# Atmega328p_Breakout.net
KiCad netlist of a schematic drawn in Altium Designer
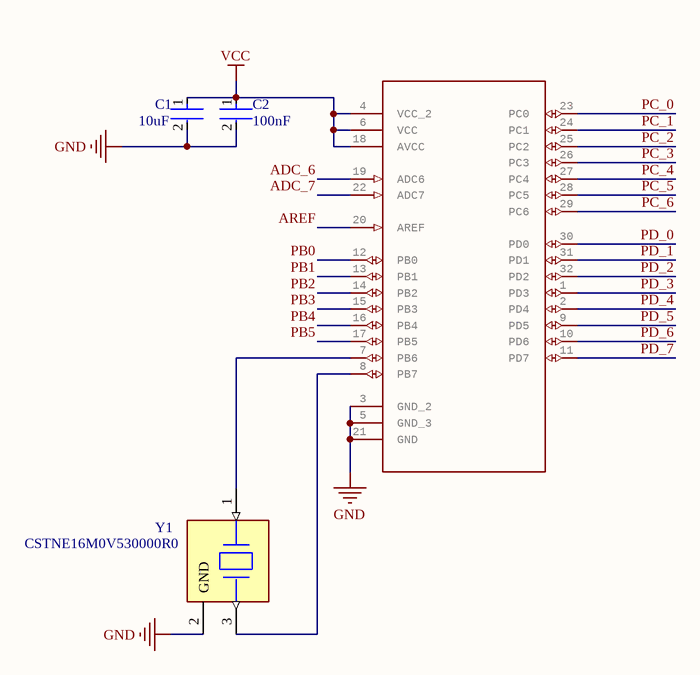
[diagram p0: Atmega328p_Breakout.SchDoc]

(export (version "E")
  (design (tool "Eeschema 10.0.6"))
  (components
    (comp (ref "C1")
      (value "10uF")
      (footprint "FP-CC0805-0_85-MFG")
      (description "CAP CER 0.1UF 50V X7R 0805")
      (fields (field (name "TOLERANCE") "0.1") (field (name "MANUFACTURER PART NUMBER") "CC0805KRX7R9BB104"))
      (libsource (lib "Altium Content Vault") (part "11868f565c42a9108669ba33697ecf6"))
    )
    (comp (ref "C2")
      (value "100nF")
      (footprint "FP-CC0805-0_85-MFG")
      (description "CAP CER 0.1UF 50V X7R 0805")
      (fields (field (name "TOLERANCE") "0.1") (field (name "MANUFACTURER PART NUMBER") "CC0805KRX7R9BB104"))
      (libsource (lib "Altium Content Vault") (part "11868f565c42a9108669ba33697ecf6"))
    )
    (comp (ref "U1")
      (value "ATMEL-ATMEGA328P-AU_ATMEGA328P-AU")
      (footprint "ATMEL-ATMEGA328P-AU_QFP80P900X900X120-32N")
      (fields (field (name "MPN") "ATMEGA328P-AU") (field (name "LIBRARYNAME") "AmbaSat-1v1-01-NO-solar"))
      (libsource (lib "Chip_kz85") (part "ATMEL-ATMEGA328P-AU_ATMEGA328P-AU"))
    )
    (comp (ref "Y1")
      (value "CSTNE16M0V530000R0")
      (footprint "FP-CSTNE16M0V530000R0-MFG")
      (description "16MHz Ceramic Resonator Built in Capacitor 15pF ±0.3% 40 Ohms -40°C ~ 85°C Surface Mount")
      (fields (field (name "TOLERANCE") "0.5%"))
      (libsource (lib "Altium Content Vault") (part "f88508b02107a2c8e6f46217c19d2b8"))
    )
  )
  (nets
    (net (code "1") (name "/ADC_6") (class "Default")
      (node (ref "U1") (pin "19") (pinfunction "ADC6_19") (pintype "input"))
    )
    (net (code "2") (name "/ADC_7") (class "Default")
      (node (ref "U1") (pin "22") (pinfunction "ADC7_22") (pintype "input"))
    )
    (net (code "3") (name "/AREF") (class "Default")
      (node (ref "U1") (pin "20") (pinfunction "AREF_20") (pintype "input"))
    )
    (net (code "4") (name "/PB0") (class "Default")
      (node (ref "U1") (pin "12") (pinfunction "PB0_12") (pintype "bidirectional"))
    )
    (net (code "5") (name "/PB1") (class "Default")
      (node (ref "U1") (pin "13") (pinfunction "PB1_13") (pintype "bidirectional"))
    )
    (net (code "6") (name "/PB2") (class "Default")
      (node (ref "U1") (pin "14") (pinfunction "PB2_14") (pintype "bidirectional"))
    )
    (net (code "7") (name "/PB3") (class "Default")
      (node (ref "U1") (pin "15") (pinfunction "PB3_15") (pintype "bidirectional"))
    )
    (net (code "8") (name "/PB4") (class "Default")
      (node (ref "U1") (pin "16") (pinfunction "PB4_16") (pintype "bidirectional"))
    )
    (net (code "9") (name "/PB5") (class "Default")
      (node (ref "U1") (pin "17") (pinfunction "PB5_17") (pintype "bidirectional"))
    )
    (net (code "10") (name "/PC_0") (class "Default")
      (node (ref "U1") (pin "23") (pinfunction "PC0_23") (pintype "bidirectional"))
    )
    (net (code "11") (name "/PC_1") (class "Default")
      (node (ref "U1") (pin "24") (pinfunction "PC1_24") (pintype "bidirectional"))
    )
    (net (code "12") (name "/PC_2") (class "Default")
      (node (ref "U1") (pin "25") (pinfunction "PC2_25") (pintype "bidirectional"))
    )
    (net (code "13") (name "/PC_3") (class "Default")
      (node (ref "U1") (pin "26") (pinfunction "PC3_26") (pintype "bidirectional"))
    )
    (net (code "14") (name "/PC_4") (class "Default")
      (node (ref "U1") (pin "27") (pinfunction "PC4_27") (pintype "bidirectional"))
    )
    (net (code "15") (name "/PC_5") (class "Default")
      (node (ref "U1") (pin "28") (pinfunction "PC5_28") (pintype "bidirectional"))
    )
    (net (code "16") (name "/PC_6") (class "Default")
      (node (ref "U1") (pin "29") (pinfunction "PC6_29") (pintype "bidirectional"))
    )
    (net (code "17") (name "/PD_0") (class "Default")
      (node (ref "U1") (pin "30") (pinfunction "PD0_30") (pintype "bidirectional"))
    )
    (net (code "18") (name "/PD_1") (class "Default")
      (node (ref "U1") (pin "31") (pinfunction "PD1_31") (pintype "bidirectional"))
    )
    (net (code "19") (name "/PD_2") (class "Default")
      (node (ref "U1") (pin "32") (pinfunction "PD2_32") (pintype "bidirectional"))
    )
    (net (code "20") (name "/PD_3") (class "Default")
      (node (ref "U1") (pin "1") (pinfunction "PD3_1") (pintype "bidirectional"))
    )
    (net (code "21") (name "/PD_4") (class "Default")
      (node (ref "U1") (pin "2") (pinfunction "PD4_2") (pintype "bidirectional"))
    )
    (net (code "22") (name "/PD_5") (class "Default")
      (node (ref "U1") (pin "9") (pinfunction "PD5_9") (pintype "bidirectional"))
    )
    (net (code "23") (name "/PD_6") (class "Default")
      (node (ref "U1") (pin "10") (pinfunction "PD6_10") (pintype "bidirectional"))
    )
    (net (code "24") (name "/PD_7") (class "Default")
      (node (ref "U1") (pin "11") (pinfunction "PD7_11") (pintype "bidirectional"))
    )
    (net (code "25") (name "GND") (class "Default")
      (node (ref "C1") (pin "2") (pinfunction "2_2") (pintype "passive"))
      (node (ref "C2") (pin "2") (pinfunction "2_2") (pintype "passive"))
      (node (ref "U1") (pin "21") (pinfunction "GND_21") (pintype "passive"))
      (node (ref "U1") (pin "3") (pinfunction "GND_2_3") (pintype "passive"))
      (node (ref "U1") (pin "5") (pinfunction "GND_3_5") (pintype "passive"))
      (node (ref "Y1") (pin "2") (pinfunction "GND_2") (pintype "power_in"))
    )
    (net (code "26") (name "Net-(U1-PB6)") (class "Default")
      (node (ref "U1") (pin "7") (pinfunction "PB6_7") (pintype "bidirectional"))
      (node (ref "Y1") (pin "1") (pinfunction "Input_1") (pintype "input"))
    )
    (net (code "27") (name "Net-(U1-PB7)") (class "Default")
      (node (ref "U1") (pin "8") (pinfunction "PB7_8") (pintype "bidirectional"))
      (node (ref "Y1") (pin "3") (pinfunction "Output_3") (pintype "output"))
    )
    (net (code "28") (name "VCC") (class "Default")
      (node (ref "C1") (pin "1") (pinfunction "1_1") (pintype "passive"))
      (node (ref "C2") (pin "1") (pinfunction "1_1") (pintype "passive"))
      (node (ref "U1") (pin "18") (pinfunction "AVCC_18") (pintype "power_in"))
      (node (ref "U1") (pin "4") (pinfunction "VCC_2_4") (pintype "power_in"))
      (node (ref "U1") (pin "6") (pinfunction "VCC_6") (pintype "power_in"))
    )
  )
)
